# schema2.net
KiCad netlist of a schematic drawn in EAGLE
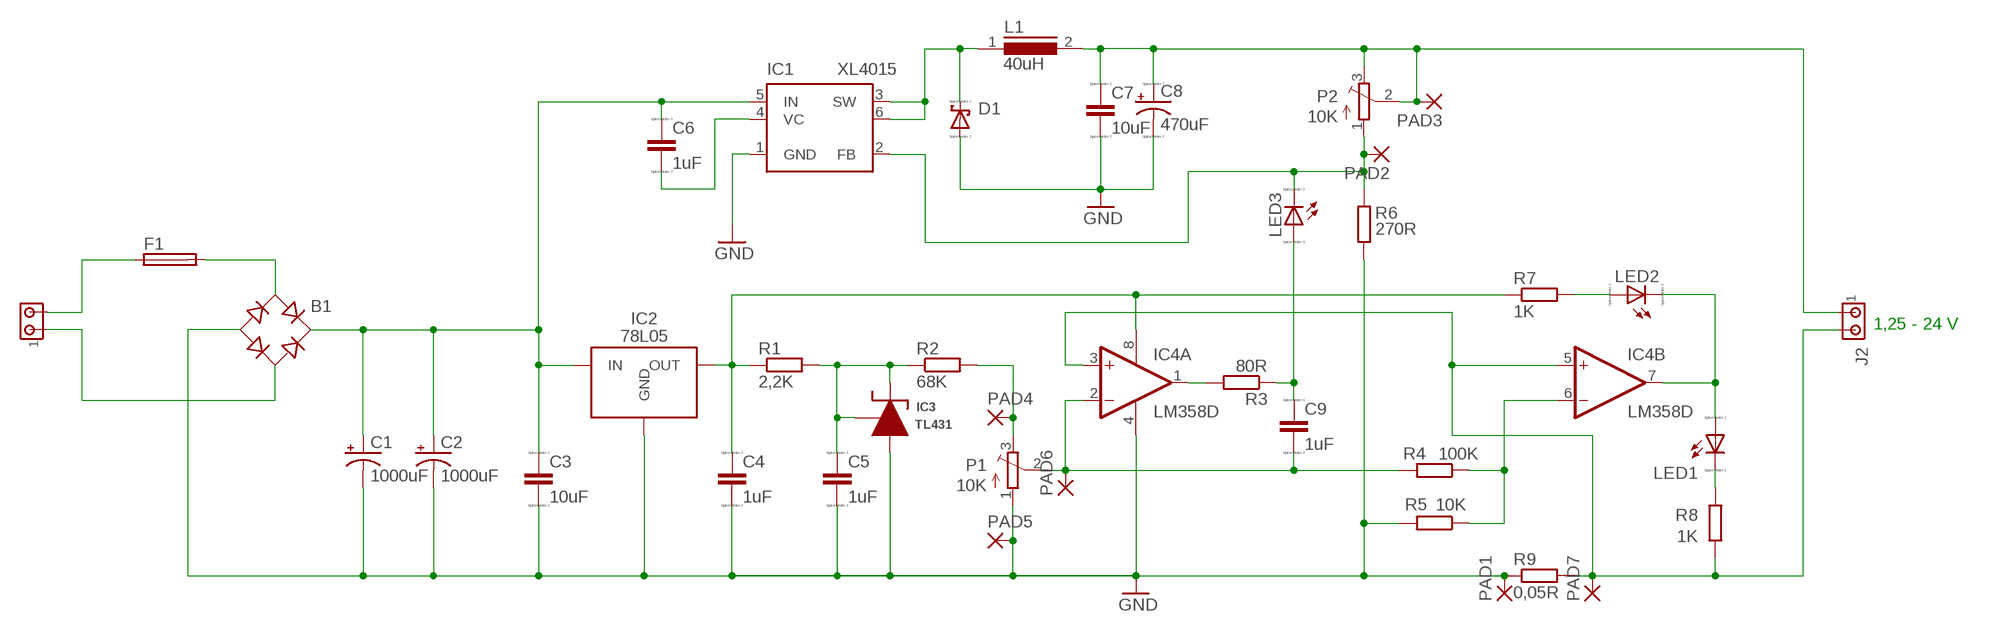
[diagram p0: schematic, sheet 1]

(export (version "E")
  (design (tool "Eeschema 10.0.6"))
  (components
    (comp (ref "B1")
      (value "RECTIFIER-2KBP")
      (footprint "eagle-import:2KBP")
      (libsource (lib "eagle-import") (part "RECTIFIER-2KBP"))
    )
    (comp (ref "C1")
      (value "1000uF")
      (footprint "eagle-import:E5-10,5")
      (libsource (lib "eagle-import") (part "CPOL-USE5-10.5"))
    )
    (comp (ref "C2")
      (value "1000uF")
      (footprint "eagle-import:E5-10,5")
      (libsource (lib "eagle-import") (part "CPOL-USE5-10.5"))
    )
    (comp (ref "C3")
      (value "10uF")
      (footprint "eagle-import:C0805")
      (libsource (lib "eagle-import") (part "C"))
    )
    (comp (ref "C4")
      (value "1uF")
      (footprint "eagle-import:C0805")
      (libsource (lib "eagle-import") (part "C"))
    )
    (comp (ref "C5")
      (value "1uF")
      (footprint "eagle-import:C0805")
      (libsource (lib "eagle-import") (part "C"))
    )
    (comp (ref "C6")
      (value "1uF")
      (footprint "eagle-import:C0805")
      (libsource (lib "eagle-import") (part "C"))
    )
    (comp (ref "C7")
      (value "10uF")
      (footprint "eagle-import:C0805")
      (libsource (lib "eagle-import") (part "C"))
    )
    (comp (ref "C8")
      (value "470uF")
      (footprint "eagle-import:153CLV-0605")
      (libsource (lib "eagle-import") (part "resistor_CPOL-US153CLV-0605"))
    )
    (comp (ref "C9")
      (value "1uF")
      (footprint "eagle-import:C0805")
      (libsource (lib "eagle-import") (part "C"))
    )
    (comp (ref "D1")
      (value "SCHOTTKY-DIODE")
      (footprint "eagle-import:DIODE_SMB")
      (libsource (lib "eagle-import") (part "SCHOTTKY-DIODE"))
    )
    (comp (ref "F1")
      (value "FUSEGSH15")
      (footprint "eagle-import:GSH15")
      (libsource (lib "eagle-import") (part "FUSEGSH15"))
    )
    (comp (ref "IC1")
      (value "XL4015")
      (footprint "eagle-import:TO263-5")
      (libsource (lib "eagle-import") (part "XL4015"))
    )
    (comp (ref "IC2")
      (value "78L05")
      (footprint "eagle-import:SOT89")
      (fields (field (name "MF") "Texas Instruments") (field (name "MPN") "UA78L05CPK"))
      (libsource (lib "eagle-import") (part "78L05?PKC"))
    )
    (comp (ref "IC3")
      (value "TL431")
      (footprint "eagle-import:SOT-23")
      (fields (field (name "MF") "Texas Instruments") (field (name "MPN") "TL431ACDBZ"))
      (libsource (lib "eagle-import") (part "TL431DBZAC"))
    )
    (comp (ref "IC4")
      (value "LM358D")
      (footprint "eagle-import:SO08")
      (libsource (lib "eagle-import") (part "LM358D"))
    )
    (comp (ref "J1")
      (value "MTA02-156")
      (footprint "eagle-import:1X2MTA")
      (libsource (lib "eagle-import") (part "MTA02-156"))
    )
    (comp (ref "J2")
      (value "MTA02-156")
      (footprint "eagle-import:1X2MTA")
      (libsource (lib "eagle-import") (part "MTA02-156"))
    )
    (comp (ref "L1")
      (value "40uH")
      (footprint "eagle-import:ED16")
      (libsource (lib "eagle-import") (part "ED16"))
    )
    (comp (ref "LED1")
      (value "LED_E")
      (footprint "eagle-import:LED_1206")
      (libsource (lib "eagle-import") (part "LED_E"))
    )
    (comp (ref "LED2")
      (value "LED_E")
      (footprint "eagle-import:LED_1206")
      (libsource (lib "eagle-import") (part "LED_E"))
    )
    (comp (ref "LED3")
      (value "LED_E")
      (footprint "eagle-import:LED_1206")
      (libsource (lib "eagle-import") (part "LED_E"))
    )
    (comp (ref "P1")
      (value "10K")
      (footprint "eagle-import:3223G")
      (libsource (lib "eagle-import") (part "TRIM_EU-3223G"))
    )
    (comp (ref "P2")
      (value "10K")
      (footprint "eagle-import:3223G")
      (libsource (lib "eagle-import") (part "TRIM_EU-3223G"))
    )
    (comp (ref "PAD1")
      (value "2,15/1,0")
      (footprint "eagle-import:2,15_1,0")
      (libsource (lib "eagle-import") (part "2,15/1,0"))
    )
    (comp (ref "PAD2")
      (value "2,15/1,0")
      (footprint "eagle-import:2,15_1,0")
      (libsource (lib "eagle-import") (part "2,15/1,0"))
    )
    (comp (ref "PAD3")
      (value "2,15/1,0")
      (footprint "eagle-import:2,15_1,0")
      (libsource (lib "eagle-import") (part "2,15/1,0"))
    )
    (comp (ref "PAD4")
      (value "2,15/1,0")
      (footprint "eagle-import:2,15_1,0")
      (libsource (lib "eagle-import") (part "2,15/1,0"))
    )
    (comp (ref "PAD5")
      (value "2,15/1,0")
      (footprint "eagle-import:2,15_1,0")
      (libsource (lib "eagle-import") (part "2,15/1,0"))
    )
    (comp (ref "PAD6")
      (value "2,15/1,0")
      (footprint "eagle-import:2,15_1,0")
      (libsource (lib "eagle-import") (part "2,15/1,0"))
    )
    (comp (ref "PAD7")
      (value "2,15/1,0")
      (footprint "eagle-import:2,15_1,0")
      (libsource (lib "eagle-import") (part "2,15/1,0"))
    )
    (comp (ref "R1")
      (value "2,2K")
      (footprint "eagle-import:M0805")
      (libsource (lib "eagle-import") (part "R-EU_M0805"))
    )
    (comp (ref "R2")
      (value "68K")
      (footprint "eagle-import:M0805")
      (libsource (lib "eagle-import") (part "R-EU_M0805"))
    )
    (comp (ref "R3")
      (value "80R")
      (footprint "eagle-import:M0805")
      (libsource (lib "eagle-import") (part "R-EU_M0805"))
    )
    (comp (ref "R4")
      (value "100K")
      (footprint "eagle-import:M0805")
      (libsource (lib "eagle-import") (part "R-EU_M0805"))
    )
    (comp (ref "R5")
      (value "10K")
      (footprint "eagle-import:M0805")
      (libsource (lib "eagle-import") (part "R-EU_M0805"))
    )
    (comp (ref "R6")
      (value "270R")
      (footprint "eagle-import:M0805")
      (libsource (lib "eagle-import") (part "R-EU_M0805"))
    )
    (comp (ref "R7")
      (value "1K")
      (footprint "eagle-import:M0805")
      (libsource (lib "eagle-import") (part "R-EU_M0805"))
    )
    (comp (ref "R8")
      (value "1K")
      (footprint "eagle-import:M0805")
      (libsource (lib "eagle-import") (part "R-EU_M0805"))
    )
    (comp (ref "R9")
      (value "0,05R")
      (footprint "eagle-import:R2512")
      (libsource (lib "eagle-import") (part "RR2512"))
    )
  )
  (nets
    (net (code "1") (name "GND") (class "Default")
      (node (ref "B1") (pin "-") (pinfunction "-_-") (pintype "passive"))
      (node (ref "C1") (pin "-") (pinfunction "-_-") (pintype "passive"))
      (node (ref "C2") (pin "-") (pinfunction "-_-") (pintype "passive"))
      (node (ref "C3") (pin "2") (pinfunction "2_2") (pintype "passive"))
      (node (ref "C4") (pin "2") (pinfunction "2_2") (pintype "passive"))
      (node (ref "C5") (pin "2") (pinfunction "2_2") (pintype "passive"))
      (node (ref "C7") (pin "2") (pinfunction "2_2") (pintype "passive"))
      (node (ref "C8") (pin "-") (pinfunction "-_-") (pintype "passive"))
      (node (ref "D1") (pin "A") (pinfunction "C_A") (pintype "passive"))
      (node (ref "IC1") (pin "1") (pinfunction "GND_1") (pintype "bidirectional"))
      (node (ref "IC2") (pin "2") (pinfunction "GND_2") (pintype "power_in"))
      (node (ref "IC2") (pin "2@1") (pinfunction "GND_2@1") (pintype "power_in"))
      (node (ref "IC3") (pin "3") (pinfunction "ANODE_3") (pintype "power_in"))
      (node (ref "IC4") (pin "4") (pinfunction "V-_4") (pintype "power_in"))
      (node (ref "P1") (pin "1") (pinfunction "A_1") (pintype "passive"))
      (node (ref "PAD1") (pin "1") (pinfunction "P_1") (pintype "passive"))
      (node (ref "PAD5") (pin "1") (pinfunction "P_1") (pintype "passive"))
      (node (ref "R5") (pin "2") (pinfunction "2_2") (pintype "passive"))
      (node (ref "R6") (pin "1") (pinfunction "1_1") (pintype "passive"))
      (node (ref "R9") (pin "1") (pinfunction "1_1") (pintype "passive"))
    )
    (net (code "2") (name "Net-(B1-PadAC1)") (class "Default")
      (node (ref "B1") (pin "AC1") (pinfunction "AC1_AC1") (pintype "passive"))
      (node (ref "F1") (pin "2") (pinfunction "2_2") (pintype "passive"))
    )
    (net (code "3") (name "Net-(C9-Pad1)") (class "Default")
      (node (ref "C9") (pin "1") (pinfunction "1_1") (pintype "passive"))
      (node (ref "LED3") (pin "A") (pinfunction "A_A") (pintype "passive"))
      (node (ref "R3") (pin "1") (pinfunction "1_1") (pintype "passive"))
    )
    (net (code "4") (name "Net-(D1-A)") (class "Default")
      (node (ref "D1") (pin "C") (pinfunction "A_C") (pintype "passive"))
      (node (ref "IC1") (pin "3") (pinfunction "SW_3") (pintype "output"))
      (node (ref "IC1") (pin "6") (pinfunction "SW_6") (pintype "power_in"))
      (node (ref "L1") (pin "1") (pinfunction "1_1") (pintype "passive"))
    )
    (net (code "5") (name "Net-(IC1-FB)") (class "Default")
      (node (ref "IC1") (pin "2") (pinfunction "FB_2") (pintype "input"))
      (node (ref "LED3") (pin "C") (pinfunction "C_C") (pintype "passive"))
      (node (ref "P2") (pin "1") (pinfunction "A_1") (pintype "passive"))
      (node (ref "PAD2") (pin "1") (pinfunction "P_1") (pintype "passive"))
      (node (ref "R6") (pin "2") (pinfunction "2_2") (pintype "passive"))
    )
    (net (code "6") (name "Net-(IC1-IN)") (class "Default")
      (node (ref "B1") (pin "+") (pinfunction "+_+") (pintype "passive"))
      (node (ref "C1") (pin "+") (pinfunction "+_+") (pintype "passive"))
      (node (ref "C2") (pin "+") (pinfunction "+_+") (pintype "passive"))
      (node (ref "C3") (pin "1") (pinfunction "1_1") (pintype "passive"))
      (node (ref "C6") (pin "1") (pinfunction "1_1") (pintype "passive"))
      (node (ref "IC1") (pin "5") (pinfunction "IN_5") (pintype "input"))
      (node (ref "IC2") (pin "3") (pinfunction "IN_3") (pintype "input"))
    )
    (net (code "7") (name "Net-(IC1-VC)") (class "Default")
      (node (ref "C6") (pin "2") (pinfunction "2_2") (pintype "passive"))
      (node (ref "IC1") (pin "4") (pinfunction "VC_4") (pintype "input"))
    )
    (net (code "8") (name "Net-(IC2-OUT)") (class "Default")
      (node (ref "C4") (pin "1") (pinfunction "1_1") (pintype "passive"))
      (node (ref "IC2") (pin "1") (pinfunction "OUT_1") (pintype "output"))
      (node (ref "IC4") (pin "8") (pinfunction "V+_8") (pintype "power_in"))
      (node (ref "R1") (pin "1") (pinfunction "1_1") (pintype "passive"))
      (node (ref "R7") (pin "1") (pinfunction "1_1") (pintype "passive"))
    )
    (net (code "9") (name "Net-(IC3-CATHODE)") (class "Default")
      (node (ref "C5") (pin "1") (pinfunction "1_1") (pintype "passive"))
      (node (ref "IC3") (pin "1") (pinfunction "CATHODE_1") (pintype "bidirectional"))
      (node (ref "IC3") (pin "2") (pinfunction "REF_2") (pintype "input"))
      (node (ref "R1") (pin "2") (pinfunction "2_2") (pintype "passive"))
      (node (ref "R2") (pin "1") (pinfunction "1_1") (pintype "passive"))
    )
    (net (code "10") (name "Net-(IC4A-+IN)") (class "Default")
      (node (ref "IC4") (pin "3") (pinfunction "+IN_3") (pintype "input"))
      (node (ref "IC4") (pin "5") (pinfunction "+IN_5") (pintype "input"))
      (node (ref "J2") (pin "1") (pinfunction "2_1") (pintype "passive"))
      (node (ref "PAD7") (pin "1") (pinfunction "P_1") (pintype "passive"))
      (node (ref "R8") (pin "1") (pinfunction "1_1") (pintype "passive"))
      (node (ref "R9") (pin "2") (pinfunction "2_2") (pintype "passive"))
    )
    (net (code "11") (name "Net-(IC4A--IN)") (class "Default")
      (node (ref "C9") (pin "2") (pinfunction "2_2") (pintype "passive"))
      (node (ref "IC4") (pin "2") (pinfunction "-IN_2") (pintype "input"))
      (node (ref "P1") (pin "2") (pinfunction "S_2") (pintype "passive"))
      (node (ref "PAD6") (pin "1") (pinfunction "P_1") (pintype "passive"))
      (node (ref "R4") (pin "2") (pinfunction "2_2") (pintype "passive"))
    )
    (net (code "12") (name "Net-(IC4A-OUT)") (class "Default")
      (node (ref "IC4") (pin "1") (pinfunction "OUT_1") (pintype "output"))
      (node (ref "R3") (pin "2") (pinfunction "2_2") (pintype "passive"))
    )
    (net (code "13") (name "Net-(IC4B--IN)") (class "Default")
      (node (ref "IC4") (pin "6") (pinfunction "-IN_6") (pintype "input"))
      (node (ref "R4") (pin "1") (pinfunction "1_1") (pintype "passive"))
      (node (ref "R5") (pin "1") (pinfunction "1_1") (pintype "passive"))
    )
    (net (code "14") (name "Net-(IC4B-OUT)") (class "Default")
      (node (ref "IC4") (pin "7") (pinfunction "OUT_7") (pintype "output"))
      (node (ref "LED1") (pin "A") (pinfunction "A_A") (pintype "passive"))
      (node (ref "LED2") (pin "C") (pinfunction "C_C") (pintype "passive"))
    )
    (net (code "15") (name "Net-(J1-1)") (class "Default")
      (node (ref "B1") (pin "AC2") (pinfunction "AC2_AC2") (pintype "passive"))
      (node (ref "J1") (pin "2") (pinfunction "1_2") (pintype "passive"))
    )
    (net (code "16") (name "Net-(J1-2)") (class "Default")
      (node (ref "F1") (pin "1") (pinfunction "1_1") (pintype "passive"))
      (node (ref "J1") (pin "1") (pinfunction "2_1") (pintype "passive"))
    )
    (net (code "17") (name "Net-(J2-1)") (class "Default")
      (node (ref "C7") (pin "1") (pinfunction "1_1") (pintype "passive"))
      (node (ref "C8") (pin "+") (pinfunction "+_+") (pintype "passive"))
      (node (ref "J2") (pin "2") (pinfunction "1_2") (pintype "passive"))
      (node (ref "L1") (pin "2") (pinfunction "2_2") (pintype "passive"))
      (node (ref "P2") (pin "2") (pinfunction "S_2") (pintype "passive"))
      (node (ref "P2") (pin "3") (pinfunction "E_3") (pintype "passive"))
      (node (ref "PAD3") (pin "1") (pinfunction "P_1") (pintype "passive"))
    )
    (net (code "18") (name "Net-(LED1-PadC)") (class "Default")
      (node (ref "LED1") (pin "C") (pinfunction "C_C") (pintype "passive"))
      (node (ref "R8") (pin "2") (pinfunction "2_2") (pintype "passive"))
    )
    (net (code "19") (name "Net-(LED2-PadA)") (class "Default")
      (node (ref "LED2") (pin "A") (pinfunction "A_A") (pintype "passive"))
      (node (ref "R7") (pin "2") (pinfunction "2_2") (pintype "passive"))
    )
    (net (code "20") (name "Net-(P1-E)") (class "Default")
      (node (ref "P1") (pin "3") (pinfunction "E_3") (pintype "passive"))
      (node (ref "PAD4") (pin "1") (pinfunction "P_1") (pintype "passive"))
      (node (ref "R2") (pin "2") (pinfunction "2_2") (pintype "passive"))
    )
  )
)
